# 14sbms_sch.net
KiCad netlist of a schematic drawn in EAGLE
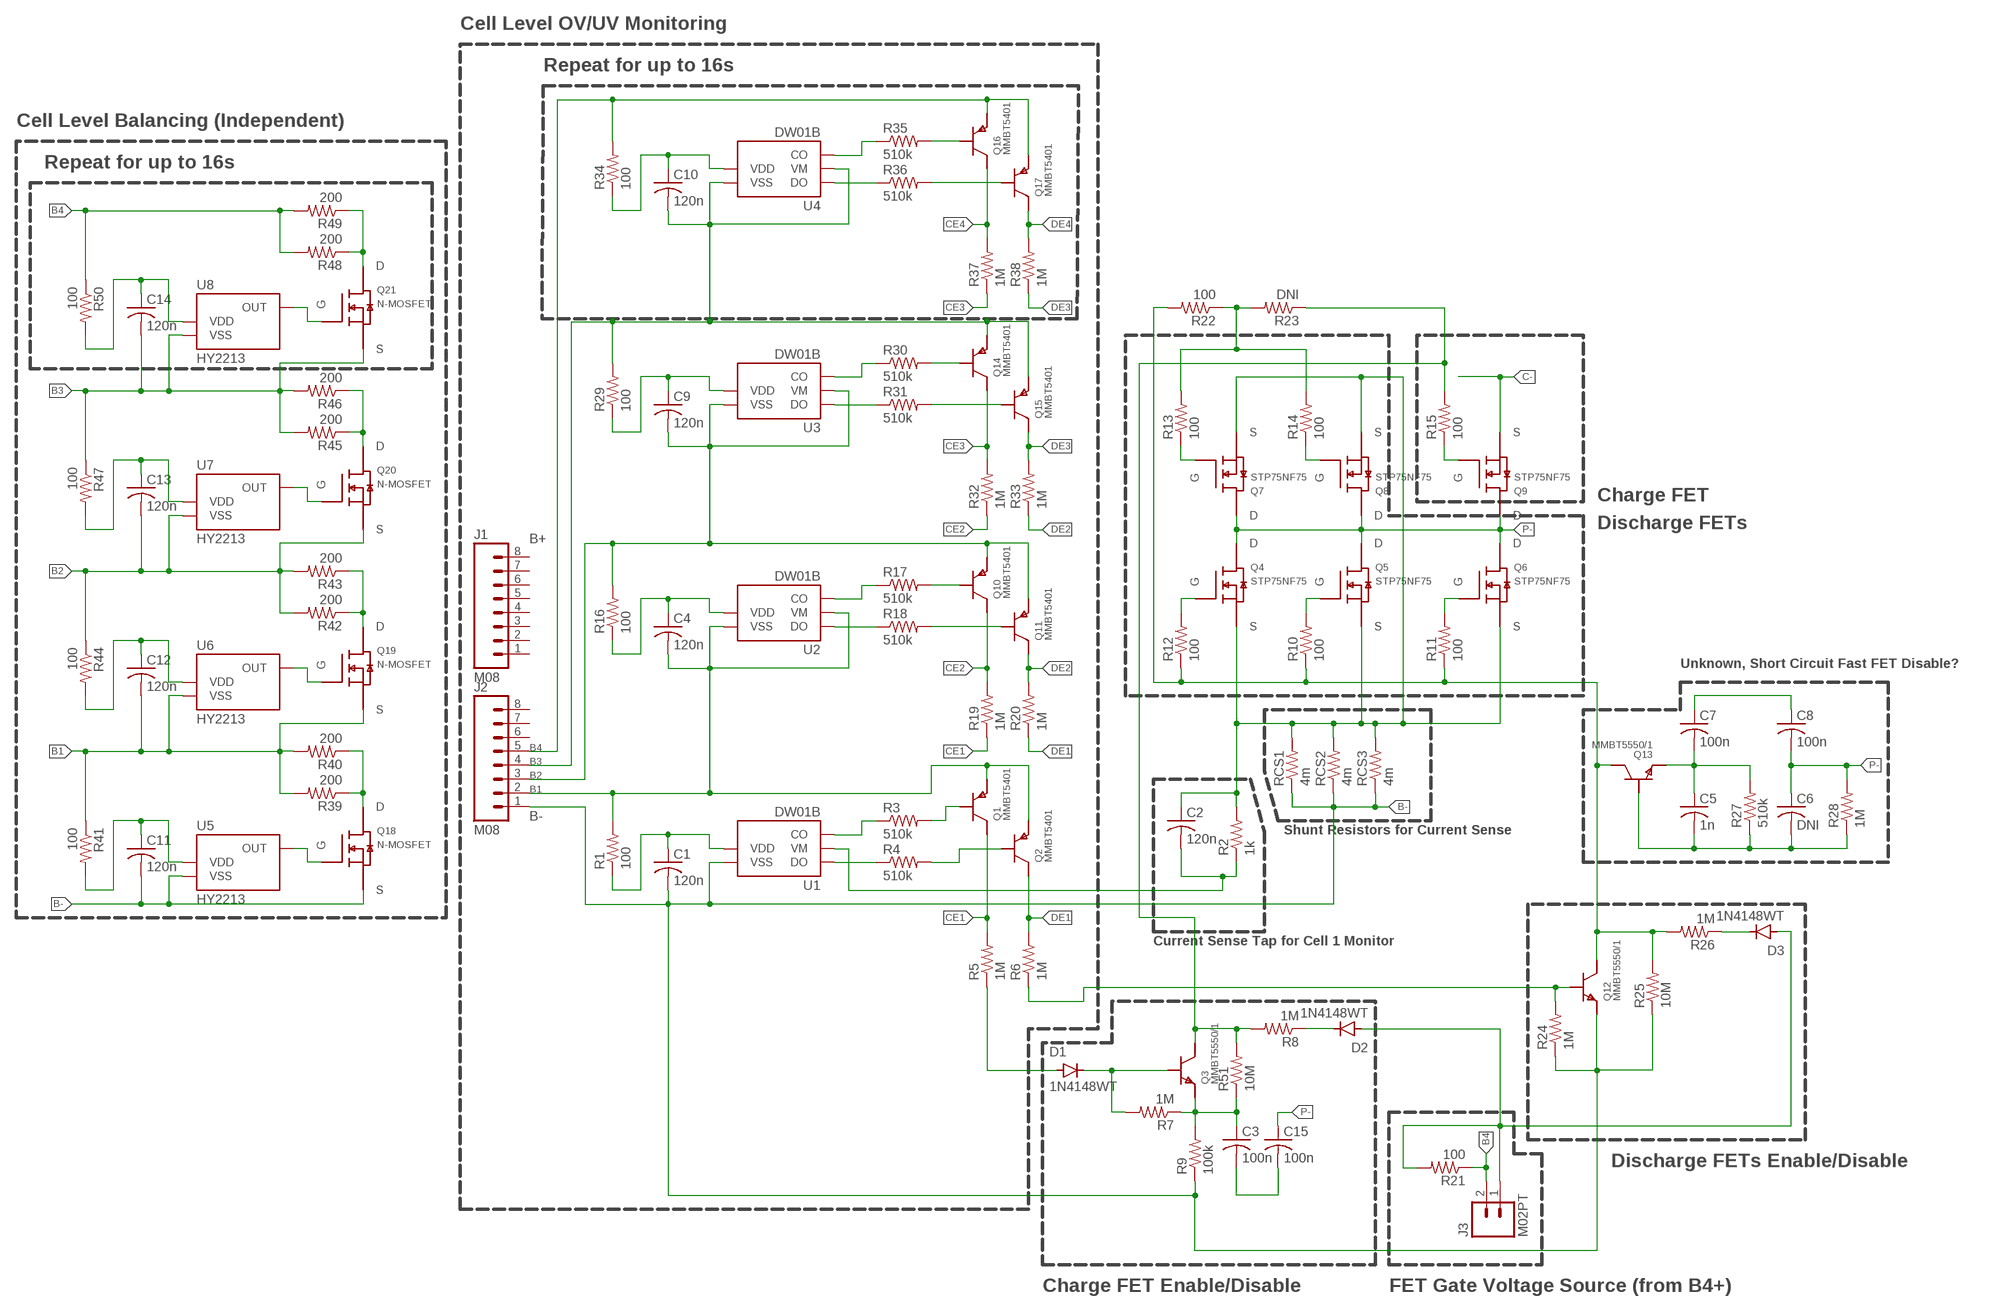
[diagram p0: schematic, sheet 1]

(export (version "E")
  (design (tool "Eeschema 10.0.6"))
  (components
    (comp (ref "C1")
      (value "120n")
      (footprint "eagle-import:C0603")
      (libsource (lib "eagle-import") (part "C-USC0603"))
    )
    (comp (ref "C2")
      (value "120n")
      (footprint "eagle-import:C0603")
      (libsource (lib "eagle-import") (part "C-USC0603"))
    )
    (comp (ref "C3")
      (value "100n")
      (footprint "eagle-import:C0603")
      (libsource (lib "eagle-import") (part "C-USC0603"))
    )
    (comp (ref "C4")
      (value "120n")
      (footprint "eagle-import:C0603")
      (libsource (lib "eagle-import") (part "C-USC0603"))
    )
    (comp (ref "C5")
      (value "1n")
      (footprint "eagle-import:C0603")
      (libsource (lib "eagle-import") (part "C-USC0603"))
    )
    (comp (ref "C6")
      (value "DNI")
      (footprint "eagle-import:C0603")
      (libsource (lib "eagle-import") (part "C-USC0603"))
    )
    (comp (ref "C7")
      (value "100n")
      (footprint "eagle-import:C0805")
      (libsource (lib "eagle-import") (part "C-USC0805"))
    )
    (comp (ref "C8")
      (value "100n")
      (footprint "eagle-import:C0805")
      (libsource (lib "eagle-import") (part "C-USC0805"))
    )
    (comp (ref "C9")
      (value "120n")
      (footprint "eagle-import:C0603")
      (libsource (lib "eagle-import") (part "C-USC0603"))
    )
    (comp (ref "C10")
      (value "120n")
      (footprint "eagle-import:C0603")
      (libsource (lib "eagle-import") (part "C-USC0603"))
    )
    (comp (ref "C11")
      (value "120n")
      (footprint "eagle-import:C0603")
      (libsource (lib "eagle-import") (part "C-USC0603"))
    )
    (comp (ref "C12")
      (value "120n")
      (footprint "eagle-import:C0603")
      (libsource (lib "eagle-import") (part "C-USC0603"))
    )
    (comp (ref "C13")
      (value "120n")
      (footprint "eagle-import:C0603")
      (libsource (lib "eagle-import") (part "C-USC0603"))
    )
    (comp (ref "C14")
      (value "120n")
      (footprint "eagle-import:C0603")
      (libsource (lib "eagle-import") (part "C-USC0603"))
    )
    (comp (ref "C15")
      (value "100n")
      (footprint "eagle-import:C0603")
      (libsource (lib "eagle-import") (part "C-USC0603"))
    )
    (comp (ref "D1")
      (value "1N4148WT")
      (footprint "eagle-import:SOD523")
      (libsource (lib "eagle-import") (part "1N4148WT"))
    )
    (comp (ref "D2")
      (value "1N4148WT")
      (footprint "eagle-import:SOD523")
      (libsource (lib "eagle-import") (part "1N4148WT"))
    )
    (comp (ref "D3")
      (value "1N4148WT")
      (footprint "eagle-import:SOD523")
      (libsource (lib "eagle-import") (part "1N4148WT"))
    )
    (comp (ref "J1")
      (value "M08")
      (footprint "eagle-import:S8B-XH-A")
      (libsource (lib "eagle-import") (part "M08"))
    )
    (comp (ref "J2")
      (value "M08")
      (footprint "eagle-import:S8B-XH-A")
      (libsource (lib "eagle-import") (part "M08"))
    )
    (comp (ref "J3")
      (value "M02PT")
      (footprint "eagle-import:PHOENIXCONTACT1935161")
      (libsource (lib "eagle-import") (part "M02PT"))
    )
    (comp (ref "Q1")
      (value "MMBT5401")
      (footprint "eagle-import:SOT23")
      (libsource (lib "eagle-import") (part "MMBT5401"))
    )
    (comp (ref "Q2")
      (value "MMBT5401")
      (footprint "eagle-import:SOT23")
      (libsource (lib "eagle-import") (part "MMBT5401"))
    )
    (comp (ref "Q3")
      (value "MMBT5550/1")
      (footprint "eagle-import:SOT23")
      (libsource (lib "eagle-import") (part "MMBT5550/1"))
    )
    (comp (ref "Q4")
      (value "STP75NF75")
      (footprint "eagle-import:D2PAK-ST")
      (libsource (lib "eagle-import") (part "STP75NF75"))
    )
    (comp (ref "Q5")
      (value "STP75NF75")
      (footprint "eagle-import:D2PAK-ST")
      (libsource (lib "eagle-import") (part "STP75NF75"))
    )
    (comp (ref "Q6")
      (value "STP75NF75")
      (footprint "eagle-import:D2PAK-ST")
      (libsource (lib "eagle-import") (part "STP75NF75"))
    )
    (comp (ref "Q7")
      (value "STP75NF75")
      (footprint "eagle-import:D2PAK-ST")
      (libsource (lib "eagle-import") (part "STP75NF75"))
    )
    (comp (ref "Q8")
      (value "STP75NF75")
      (footprint "eagle-import:D2PAK-ST")
      (libsource (lib "eagle-import") (part "STP75NF75"))
    )
    (comp (ref "Q9")
      (value "STP75NF75")
      (footprint "eagle-import:D2PAK-ST")
      (libsource (lib "eagle-import") (part "STP75NF75"))
    )
    (comp (ref "Q10")
      (value "MMBT5401")
      (footprint "eagle-import:SOT23")
      (libsource (lib "eagle-import") (part "MMBT5401"))
    )
    (comp (ref "Q11")
      (value "MMBT5401")
      (footprint "eagle-import:SOT23")
      (libsource (lib "eagle-import") (part "MMBT5401"))
    )
    (comp (ref "Q12")
      (value "MMBT5550/1")
      (footprint "eagle-import:SOT23")
      (libsource (lib "eagle-import") (part "MMBT5550/1"))
    )
    (comp (ref "Q13")
      (value "MMBT5550/1")
      (footprint "eagle-import:SOT23")
      (libsource (lib "eagle-import") (part "MMBT5550/1"))
    )
    (comp (ref "Q14")
      (value "MMBT5401")
      (footprint "eagle-import:SOT23")
      (libsource (lib "eagle-import") (part "MMBT5401"))
    )
    (comp (ref "Q15")
      (value "MMBT5401")
      (footprint "eagle-import:SOT23")
      (libsource (lib "eagle-import") (part "MMBT5401"))
    )
    (comp (ref "Q16")
      (value "MMBT5401")
      (footprint "eagle-import:SOT23")
      (libsource (lib "eagle-import") (part "MMBT5401"))
    )
    (comp (ref "Q17")
      (value "MMBT5401")
      (footprint "eagle-import:SOT23")
      (libsource (lib "eagle-import") (part "MMBT5401"))
    )
    (comp (ref "Q18")
      (value "N-MOSFET")
      (footprint "eagle-import:SOT23")
      (libsource (lib "eagle-import") (part "N-MOSFET"))
    )
    (comp (ref "Q19")
      (value "N-MOSFET")
      (footprint "eagle-import:SOT23")
      (libsource (lib "eagle-import") (part "N-MOSFET"))
    )
    (comp (ref "Q20")
      (value "N-MOSFET")
      (footprint "eagle-import:SOT23")
      (libsource (lib "eagle-import") (part "N-MOSFET"))
    )
    (comp (ref "Q21")
      (value "N-MOSFET")
      (footprint "eagle-import:SOT23")
      (libsource (lib "eagle-import") (part "N-MOSFET"))
    )
    (comp (ref "R1")
      (value "100")
      (footprint "eagle-import:R0603")
      (libsource (lib "eagle-import") (part "R-US_R0603"))
    )
    (comp (ref "R2")
      (value "1k")
      (footprint "eagle-import:R0603")
      (libsource (lib "eagle-import") (part "R-US_R0603"))
    )
    (comp (ref "R3")
      (value "510k")
      (footprint "eagle-import:R0603")
      (libsource (lib "eagle-import") (part "R-US_R0603"))
    )
    (comp (ref "R4")
      (value "510k")
      (footprint "eagle-import:R0603")
      (libsource (lib "eagle-import") (part "R-US_R0603"))
    )
    (comp (ref "R5")
      (value "1M")
      (footprint "eagle-import:R0603")
      (libsource (lib "eagle-import") (part "R-US_R0603"))
    )
    (comp (ref "R6")
      (value "1M")
      (footprint "eagle-import:R0603")
      (libsource (lib "eagle-import") (part "R-US_R0603"))
    )
    (comp (ref "R7")
      (value "1M")
      (footprint "eagle-import:R0603")
      (libsource (lib "eagle-import") (part "R-US_R0603"))
    )
    (comp (ref "R8")
      (value "1M")
      (footprint "eagle-import:R0603")
      (libsource (lib "eagle-import") (part "R-US_R0603"))
    )
    (comp (ref "R9")
      (value "100k")
      (footprint "eagle-import:R0603")
      (libsource (lib "eagle-import") (part "R-US_R0603"))
    )
    (comp (ref "R10")
      (value "100")
      (footprint "eagle-import:R0603")
      (libsource (lib "eagle-import") (part "R-US_R0603"))
    )
    (comp (ref "R11")
      (value "100")
      (footprint "eagle-import:R0603")
      (libsource (lib "eagle-import") (part "R-US_R0603"))
    )
    (comp (ref "R12")
      (value "100")
      (footprint "eagle-import:R0603")
      (libsource (lib "eagle-import") (part "R-US_R0603"))
    )
    (comp (ref "R13")
      (value "100")
      (footprint "eagle-import:R0603")
      (libsource (lib "eagle-import") (part "R-US_R0603"))
    )
    (comp (ref "R14")
      (value "100")
      (footprint "eagle-import:R0603")
      (libsource (lib "eagle-import") (part "R-US_R0603"))
    )
    (comp (ref "R15")
      (value "100")
      (footprint "eagle-import:R0603")
      (libsource (lib "eagle-import") (part "R-US_R0603"))
    )
    (comp (ref "R16")
      (value "100")
      (footprint "eagle-import:R0603")
      (libsource (lib "eagle-import") (part "R-US_R0603"))
    )
    (comp (ref "R17")
      (value "510k")
      (footprint "eagle-import:R0603")
      (libsource (lib "eagle-import") (part "R-US_R0603"))
    )
    (comp (ref "R18")
      (value "510k")
      (footprint "eagle-import:R0603")
      (libsource (lib "eagle-import") (part "R-US_R0603"))
    )
    (comp (ref "R19")
      (value "1M")
      (footprint "eagle-import:R0603")
      (libsource (lib "eagle-import") (part "R-US_R0603"))
    )
    (comp (ref "R20")
      (value "1M")
      (footprint "eagle-import:R0603")
      (libsource (lib "eagle-import") (part "R-US_R0603"))
    )
    (comp (ref "R21")
      (value "100")
      (footprint "eagle-import:R0603")
      (libsource (lib "eagle-import") (part "R-US_R0603"))
    )
    (comp (ref "R22")
      (value "100")
      (footprint "eagle-import:R0603")
      (libsource (lib "eagle-import") (part "R-US_R0603"))
    )
    (comp (ref "R23")
      (value "DNI")
      (footprint "eagle-import:R0603")
      (libsource (lib "eagle-import") (part "R-US_R0603"))
    )
    (comp (ref "R24")
      (value "1M")
      (footprint "eagle-import:R0603")
      (libsource (lib "eagle-import") (part "R-US_R0603"))
    )
    (comp (ref "R25")
      (value "10M")
      (footprint "eagle-import:R0603")
      (libsource (lib "eagle-import") (part "R-US_R0603"))
    )
    (comp (ref "R26")
      (value "1M")
      (footprint "eagle-import:R0603")
      (libsource (lib "eagle-import") (part "R-US_R0603"))
    )
    (comp (ref "R27")
      (value "510k")
      (footprint "eagle-import:R0603")
      (libsource (lib "eagle-import") (part "R-US_R0603"))
    )
    (comp (ref "R28")
      (value "1M")
      (footprint "eagle-import:R0603")
      (libsource (lib "eagle-import") (part "R-US_R0603"))
    )
    (comp (ref "R29")
      (value "100")
      (footprint "eagle-import:R0603")
      (libsource (lib "eagle-import") (part "R-US_R0603"))
    )
    (comp (ref "R30")
      (value "510k")
      (footprint "eagle-import:R0603")
      (libsource (lib "eagle-import") (part "R-US_R0603"))
    )
    (comp (ref "R31")
      (value "510k")
      (footprint "eagle-import:R0603")
      (libsource (lib "eagle-import") (part "R-US_R0603"))
    )
    (comp (ref "R32")
      (value "1M")
      (footprint "eagle-import:R0603")
      (libsource (lib "eagle-import") (part "R-US_R0603"))
    )
    (comp (ref "R33")
      (value "1M")
      (footprint "eagle-import:R0603")
      (libsource (lib "eagle-import") (part "R-US_R0603"))
    )
    (comp (ref "R34")
      (value "100")
      (footprint "eagle-import:R0603")
      (libsource (lib "eagle-import") (part "R-US_R0603"))
    )
    (comp (ref "R35")
      (value "510k")
      (footprint "eagle-import:R0603")
      (libsource (lib "eagle-import") (part "R-US_R0603"))
    )
    (comp (ref "R36")
      (value "510k")
      (footprint "eagle-import:R0603")
      (libsource (lib "eagle-import") (part "R-US_R0603"))
    )
    (comp (ref "R37")
      (value "1M")
      (footprint "eagle-import:R0603")
      (libsource (lib "eagle-import") (part "R-US_R0603"))
    )
    (comp (ref "R38")
      (value "1M")
      (footprint "eagle-import:R0603")
      (libsource (lib "eagle-import") (part "R-US_R0603"))
    )
    (comp (ref "R39")
      (value "200")
      (footprint "eagle-import:R1206")
      (libsource (lib "eagle-import") (part "R-US_R1206"))
    )
    (comp (ref "R40")
      (value "200")
      (footprint "eagle-import:R1206")
      (libsource (lib "eagle-import") (part "R-US_R1206"))
    )
    (comp (ref "R41")
      (value "100")
      (footprint "eagle-import:R0603")
      (libsource (lib "eagle-import") (part "R-US_R0603"))
    )
    (comp (ref "R42")
      (value "200")
      (footprint "eagle-import:R1206")
      (libsource (lib "eagle-import") (part "R-US_R1206"))
    )
    (comp (ref "R43")
      (value "200")
      (footprint "eagle-import:R1206")
      (libsource (lib "eagle-import") (part "R-US_R1206"))
    )
    (comp (ref "R44")
      (value "100")
      (footprint "eagle-import:R0603")
      (libsource (lib "eagle-import") (part "R-US_R0603"))
    )
    (comp (ref "R45")
      (value "200")
      (footprint "eagle-import:R1206")
      (libsource (lib "eagle-import") (part "R-US_R1206"))
    )
    (comp (ref "R46")
      (value "200")
      (footprint "eagle-import:R1206")
      (libsource (lib "eagle-import") (part "R-US_R1206"))
    )
    (comp (ref "R47")
      (value "100")
      (footprint "eagle-import:R0603")
      (libsource (lib "eagle-import") (part "R-US_R0603"))
    )
    (comp (ref "R48")
      (value "200")
      (footprint "eagle-import:R1206")
      (libsource (lib "eagle-import") (part "R-US_R1206"))
    )
    (comp (ref "R49")
      (value "200")
      (footprint "eagle-import:R1206")
      (libsource (lib "eagle-import") (part "R-US_R1206"))
    )
    (comp (ref "R50")
      (value "100")
      (footprint "eagle-import:R0603")
      (libsource (lib "eagle-import") (part "R-US_R0603"))
    )
    (comp (ref "R51")
      (value "10M")
      (footprint "eagle-import:R0603")
      (libsource (lib "eagle-import") (part "R-US_R0603"))
    )
    (comp (ref "RCS1")
      (value "4m")
      (footprint "eagle-import:R2512")
      (libsource (lib "eagle-import") (part "R-US_R2512"))
    )
    (comp (ref "RCS2")
      (value "4m")
      (footprint "eagle-import:R2512")
      (libsource (lib "eagle-import") (part "R-US_R2512"))
    )
    (comp (ref "RCS3")
      (value "4m")
      (footprint "eagle-import:R2512")
      (libsource (lib "eagle-import") (part "R-US_R2512"))
    )
    (comp (ref "U1")
      (value "DW01B")
      (footprint "eagle-import:SOT23-6")
      (libsource (lib "eagle-import") (part "DW01B"))
    )
    (comp (ref "U2")
      (value "DW01B")
      (footprint "eagle-import:SOT23-6")
      (libsource (lib "eagle-import") (part "DW01B"))
    )
    (comp (ref "U3")
      (value "DW01B")
      (footprint "eagle-import:SOT23-6")
      (libsource (lib "eagle-import") (part "DW01B"))
    )
    (comp (ref "U4")
      (value "DW01B")
      (footprint "eagle-import:SOT23-6")
      (libsource (lib "eagle-import") (part "DW01B"))
    )
    (comp (ref "U5")
      (value "HY2213")
      (footprint "eagle-import:SOT23-6")
      (libsource (lib "eagle-import") (part "HY2213"))
    )
    (comp (ref "U6")
      (value "HY2213")
      (footprint "eagle-import:SOT23-6")
      (libsource (lib "eagle-import") (part "HY2213"))
    )
    (comp (ref "U7")
      (value "HY2213")
      (footprint "eagle-import:SOT23-6")
      (libsource (lib "eagle-import") (part "HY2213"))
    )
    (comp (ref "U8")
      (value "HY2213")
      (footprint "eagle-import:SOT23-6")
      (libsource (lib "eagle-import") (part "HY2213"))
    )
  )
  (nets
    (net (code "1") (name "B-") (class "Default")
      (node (ref "C1") (pin "2") (pinfunction "2_2") (pintype "passive"))
      (node (ref "C11") (pin "2") (pinfunction "2_2") (pintype "passive"))
      (node (ref "J2") (pin "1") (pinfunction "1_1") (pintype "passive"))
      (node (ref "Q12") (pin "2") (pinfunction "E_2") (pintype "bidirectional"))
      (node (ref "Q18") (pin "2") (pinfunction "S_2") (pintype "bidirectional"))
      (node (ref "R24") (pin "1") (pinfunction "1_1") (pintype "passive"))
      (node (ref "R25") (pin "1") (pinfunction "1_1") (pintype "passive"))
      (node (ref "R9") (pin "1") (pinfunction "1_1") (pintype "passive"))
      (node (ref "RCS1") (pin "1") (pinfunction "1_1") (pintype "passive"))
      (node (ref "RCS2") (pin "1") (pinfunction "1_1") (pintype "passive"))
      (node (ref "RCS3") (pin "1") (pinfunction "1_1") (pintype "passive"))
      (node (ref "U1") (pin "6") (pinfunction "VSS_6") (pintype "bidirectional"))
      (node (ref "U5") (pin "3") (pinfunction "VSS_3") (pintype "bidirectional"))
    )
    (net (code "2") (name "B1") (class "Default")
      (node (ref "C12") (pin "2") (pinfunction "2_2") (pintype "passive"))
      (node (ref "C4") (pin "2") (pinfunction "2_2") (pintype "passive"))
      (node (ref "J2") (pin "2") (pinfunction "2_2") (pintype "passive"))
      (node (ref "Q1") (pin "2") (pinfunction "E_2") (pintype "bidirectional"))
      (node (ref "Q19") (pin "2") (pinfunction "S_2") (pintype "bidirectional"))
      (node (ref "Q2") (pin "2") (pinfunction "E_2") (pintype "bidirectional"))
      (node (ref "R1") (pin "2") (pinfunction "2_2") (pintype "passive"))
      (node (ref "R39") (pin "2") (pinfunction "2_2") (pintype "passive"))
      (node (ref "R40") (pin "2") (pinfunction "2_2") (pintype "passive"))
      (node (ref "R41") (pin "1") (pinfunction "1_1") (pintype "passive"))
      (node (ref "U2") (pin "2") (pinfunction "VM_2") (pintype "bidirectional"))
      (node (ref "U2") (pin "6") (pinfunction "VSS_6") (pintype "bidirectional"))
      (node (ref "U6") (pin "3") (pinfunction "VSS_3") (pintype "bidirectional"))
    )
    (net (code "3") (name "B2") (class "Default")
      (node (ref "C13") (pin "2") (pinfunction "2_2") (pintype "passive"))
      (node (ref "C9") (pin "2") (pinfunction "2_2") (pintype "passive"))
      (node (ref "J2") (pin "3") (pinfunction "3_3") (pintype "passive"))
      (node (ref "Q10") (pin "2") (pinfunction "E_2") (pintype "bidirectional"))
      (node (ref "Q11") (pin "2") (pinfunction "E_2") (pintype "bidirectional"))
      (node (ref "Q20") (pin "2") (pinfunction "S_2") (pintype "bidirectional"))
      (node (ref "R16") (pin "2") (pinfunction "2_2") (pintype "passive"))
      (node (ref "R42") (pin "2") (pinfunction "2_2") (pintype "passive"))
      (node (ref "R43") (pin "2") (pinfunction "2_2") (pintype "passive"))
      (node (ref "R44") (pin "1") (pinfunction "1_1") (pintype "passive"))
      (node (ref "U3") (pin "2") (pinfunction "VM_2") (pintype "bidirectional"))
      (node (ref "U3") (pin "6") (pinfunction "VSS_6") (pintype "bidirectional"))
      (node (ref "U7") (pin "3") (pinfunction "VSS_3") (pintype "bidirectional"))
    )
    (net (code "4") (name "B3") (class "Default")
      (node (ref "C10") (pin "2") (pinfunction "2_2") (pintype "passive"))
      (node (ref "C14") (pin "2") (pinfunction "2_2") (pintype "passive"))
      (node (ref "J2") (pin "4") (pinfunction "4_4") (pintype "passive"))
      (node (ref "Q14") (pin "2") (pinfunction "E_2") (pintype "bidirectional"))
      (node (ref "Q15") (pin "2") (pinfunction "E_2") (pintype "bidirectional"))
      (node (ref "Q21") (pin "2") (pinfunction "S_2") (pintype "bidirectional"))
      (node (ref "R29") (pin "2") (pinfunction "2_2") (pintype "passive"))
      (node (ref "R45") (pin "2") (pinfunction "2_2") (pintype "passive"))
      (node (ref "R46") (pin "2") (pinfunction "2_2") (pintype "passive"))
      (node (ref "R47") (pin "1") (pinfunction "1_1") (pintype "passive"))
      (node (ref "U4") (pin "2") (pinfunction "VM_2") (pintype "bidirectional"))
      (node (ref "U4") (pin "6") (pinfunction "VSS_6") (pintype "bidirectional"))
      (node (ref "U8") (pin "3") (pinfunction "VSS_3") (pintype "bidirectional"))
    )
    (net (code "5") (name "B4") (class "Default")
      (node (ref "J2") (pin "5") (pinfunction "5_5") (pintype "passive"))
      (node (ref "J3") (pin "2") (pinfunction "2_2") (pintype "passive"))
      (node (ref "Q16") (pin "2") (pinfunction "E_2") (pintype "bidirectional"))
      (node (ref "Q17") (pin "2") (pinfunction "E_2") (pintype "bidirectional"))
      (node (ref "R21") (pin "1") (pinfunction "1_1") (pintype "passive"))
      (node (ref "R34") (pin "2") (pinfunction "2_2") (pintype "passive"))
      (node (ref "R48") (pin "2") (pinfunction "2_2") (pintype "passive"))
      (node (ref "R49") (pin "2") (pinfunction "2_2") (pintype "passive"))
      (node (ref "R50") (pin "1") (pinfunction "1_1") (pintype "passive"))
    )
    (net (code "6") (name "C-") (class "Default")
      (node (ref "Q9") (pin "3-S") (pinfunction "S_3-S") (pintype "bidirectional"))
    )
    (net (code "7") (name "CE1") (class "Default")
      (node (ref "Q1") (pin "3") (pinfunction "C_3") (pintype "bidirectional"))
      (node (ref "R19") (pin "1") (pinfunction "1_1") (pintype "passive"))
      (node (ref "R5") (pin "2") (pinfunction "2_2") (pintype "passive"))
    )
    (net (code "8") (name "CE2") (class "Default")
      (node (ref "Q10") (pin "3") (pinfunction "C_3") (pintype "bidirectional"))
      (node (ref "R19") (pin "2") (pinfunction "2_2") (pintype "passive"))
      (node (ref "R32") (pin "1") (pinfunction "1_1") (pintype "passive"))
    )
    (net (code "9") (name "CE3") (class "Default")
      (node (ref "Q14") (pin "3") (pinfunction "C_3") (pintype "bidirectional"))
      (node (ref "R32") (pin "2") (pinfunction "2_2") (pintype "passive"))
      (node (ref "R37") (pin "1") (pinfunction "1_1") (pintype "passive"))
    )
    (net (code "10") (name "CE4") (class "Default")
      (node (ref "Q16") (pin "3") (pinfunction "C_3") (pintype "bidirectional"))
      (node (ref "R37") (pin "2") (pinfunction "2_2") (pintype "passive"))
    )
    (net (code "11") (name "DE1") (class "Default")
      (node (ref "Q2") (pin "3") (pinfunction "C_3") (pintype "bidirectional"))
      (node (ref "R20") (pin "1") (pinfunction "1_1") (pintype "passive"))
      (node (ref "R6") (pin "2") (pinfunction "2_2") (pintype "passive"))
    )
    (net (code "12") (name "DE2") (class "Default")
      (node (ref "Q11") (pin "3") (pinfunction "C_3") (pintype "bidirectional"))
      (node (ref "R20") (pin "2") (pinfunction "2_2") (pintype "passive"))
      (node (ref "R33") (pin "1") (pinfunction "1_1") (pintype "passive"))
    )
    (net (code "13") (name "DE3") (class "Default")
      (node (ref "Q15") (pin "3") (pinfunction "C_3") (pintype "bidirectional"))
      (node (ref "R33") (pin "2") (pinfunction "2_2") (pintype "passive"))
      (node (ref "R38") (pin "1") (pinfunction "1_1") (pintype "passive"))
    )
    (net (code "14") (name "DE4") (class "Default")
      (node (ref "Q17") (pin "3") (pinfunction "C_3") (pintype "bidirectional"))
      (node (ref "R38") (pin "2") (pinfunction "2_2") (pintype "passive"))
    )
    (net (code "15") (name "Net-(C7-Pad1)") (class "Default")
      (node (ref "C7") (pin "1") (pinfunction "1_1") (pintype "passive"))
      (node (ref "C8") (pin "1") (pinfunction "1_1") (pintype "passive"))
    )
    (net (code "16") (name "Net-(C15-Pad2)") (class "Default")
      (node (ref "C15") (pin "2") (pinfunction "2_2") (pintype "passive"))
      (node (ref "C3") (pin "2") (pinfunction "2_2") (pintype "passive"))
    )
    (net (code "17") (name "Net-(D1-ANODE)") (class "Default")
      (node (ref "D1") (pin "A") (pinfunction "ANODE_A") (pintype "passive"))
      (node (ref "R5") (pin "1") (pinfunction "1_1") (pintype "passive"))
    )
    (net (code "18") (name "Net-(D1-CATHODE)") (class "Default")
      (node (ref "D1") (pin "K") (pinfunction "CATHODE_K") (pintype "passive"))
      (node (ref "Q3") (pin "1") (pinfunction "B_1") (pintype "bidirectional"))
      (node (ref "R7") (pin "2") (pinfunction "2_2") (pintype "passive"))
    )
    (net (code "19") (name "Net-(D2-ANODE)") (class "Default")
      (node (ref "D2") (pin "A") (pinfunction "ANODE_A") (pintype "passive"))
      (node (ref "D3") (pin "A") (pinfunction "ANODE_A") (pintype "passive"))
      (node (ref "J3") (pin "1") (pinfunction "1_1") (pintype "passive"))
      (node (ref "R21") (pin "2") (pinfunction "2_2") (pintype "passive"))
    )
    (net (code "20") (name "Net-(D2-CATHODE)") (class "Default")
      (node (ref "D2") (pin "K") (pinfunction "CATHODE_K") (pintype "passive"))
      (node (ref "R8") (pin "1") (pinfunction "1_1") (pintype "passive"))
    )
    (net (code "21") (name "Net-(D3-CATHODE)") (class "Default")
      (node (ref "D3") (pin "K") (pinfunction "CATHODE_K") (pintype "passive"))
      (node (ref "R26") (pin "1") (pinfunction "1_1") (pintype "passive"))
    )
    (net (code "22") (name "Net-(Q1-B)") (class "Default")
      (node (ref "Q1") (pin "1") (pinfunction "B_1") (pintype "bidirectional"))
      (node (ref "R3") (pin "2") (pinfunction "2_2") (pintype "passive"))
    )
    (net (code "23") (name "Net-(Q2-B)") (class "Default")
      (node (ref "Q2") (pin "1") (pinfunction "B_1") (pintype "bidirectional"))
      (node (ref "R4") (pin "2") (pinfunction "2_2") (pintype "passive"))
    )
    (net (code "24") (name "Net-(Q3-C)") (class "Default")
      (node (ref "Q3") (pin "3") (pinfunction "C_3") (pintype "bidirectional"))
      (node (ref "R15") (pin "2") (pinfunction "2_2") (pintype "passive"))
      (node (ref "R23") (pin "1") (pinfunction "1_1") (pintype "passive"))
      (node (ref "R51") (pin "2") (pinfunction "2_2") (pintype "passive"))
      (node (ref "R8") (pin "2") (pinfunction "2_2") (pintype "passive"))
    )
    (net (code "25") (name "Net-(Q3-E)") (class "Default")
      (node (ref "C3") (pin "1") (pinfunction "1_1") (pintype "passive"))
      (node (ref "Q3") (pin "2") (pinfunction "E_2") (pintype "bidirectional"))
      (node (ref "R51") (pin "1") (pinfunction "1_1") (pintype "passive"))
      (node (ref "R7") (pin "1") (pinfunction "1_1") (pintype "passive"))
      (node (ref "R9") (pin "2") (pinfunction "2_2") (pintype "passive"))
    )
    (net (code "26") (name "Net-(Q4-G)") (class "Default")
      (node (ref "Q4") (pin "1-G") (pinfunction "G_1-G") (pintype "bidirectional"))
      (node (ref "R12") (pin "2") (pinfunction "2_2") (pintype "passive"))
    )
    (net (code "27") (name "Net-(Q4-S)") (class "Default")
      (node (ref "C2") (pin "1") (pinfunction "1_1") (pintype "passive"))
      (node (ref "Q4") (pin "3-S") (pinfunction "S_3-S") (pintype "bidirectional"))
      (node (ref "Q5") (pin "3-S") (pinfunction "S_3-S") (pintype "bidirectional"))
      (node (ref "Q6") (pin "3-S") (pinfunction "S_3-S") (pintype "bidirectional"))
      (node (ref "Q7") (pin "3-S") (pinfunction "S_3-S") (pintype "bidirectional"))
      (node (ref "Q8") (pin "3-S") (pinfunction "S_3-S") (pintype "bidirectional"))
      (node (ref "R2") (pin "2") (pinfunction "2_2") (pintype "passive"))
      (node (ref "RCS1") (pin "2") (pinfunction "2_2") (pintype "passive"))
      (node (ref "RCS2") (pin "2") (pinfunction "2_2") (pintype "passive"))
      (node (ref "RCS3") (pin "2") (pinfunction "2_2") (pintype "passive"))
    )
    (net (code "28") (name "Net-(Q5-G)") (class "Default")
      (node (ref "Q5") (pin "1-G") (pinfunction "G_1-G") (pintype "bidirectional"))
      (node (ref "R10") (pin "2") (pinfunction "2_2") (pintype "passive"))
    )
    (net (code "29") (name "Net-(Q6-G)") (class "Default")
      (node (ref "Q6") (pin "1-G") (pinfunction "G_1-G") (pintype "bidirectional"))
      (node (ref "R11") (pin "2") (pinfunction "2_2") (pintype "passive"))
    )
    (net (code "30") (name "Net-(Q7-G)") (class "Default")
      (node (ref "Q7") (pin "1-G") (pinfunction "G_1-G") (pintype "bidirectional"))
      (node (ref "R13") (pin "1") (pinfunction "1_1") (pintype "passive"))
    )
    (net (code "31") (name "Net-(Q8-G)") (class "Default")
      (node (ref "Q8") (pin "1-G") (pinfunction "G_1-G") (pintype "bidirectional"))
      (node (ref "R14") (pin "1") (pinfunction "1_1") (pintype "passive"))
    )
    (net (code "32") (name "Net-(Q9-G)") (class "Default")
      (node (ref "Q9") (pin "1-G") (pinfunction "G_1-G") (pintype "bidirectional"))
      (node (ref "R15") (pin "1") (pinfunction "1_1") (pintype "passive"))
    )
    (net (code "33") (name "Net-(Q10-B)") (class "Default")
      (node (ref "Q10") (pin "1") (pinfunction "B_1") (pintype "bidirectional"))
      (node (ref "R17") (pin "2") (pinfunction "2_2") (pintype "passive"))
    )
    (net (code "34") (name "Net-(Q11-B)") (class "Default")
      (node (ref "Q11") (pin "1") (pinfunction "B_1") (pintype "bidirectional"))
      (node (ref "R18") (pin "2") (pinfunction "2_2") (pintype "passive"))
    )
    (net (code "35") (name "Net-(Q12-B)") (class "Default")
      (node (ref "Q12") (pin "1") (pinfunction "B_1") (pintype "bidirectional"))
      (node (ref "R24") (pin "2") (pinfunction "2_2") (pintype "passive"))
      (node (ref "R6") (pin "1") (pinfunction "1_1") (pintype "passive"))
    )
    (net (code "36") (name "Net-(Q12-C)") (class "Default")
      (node (ref "Q12") (pin "3") (pinfunction "C_3") (pintype "bidirectional"))
      (node (ref "Q13") (pin "3") (pinfunction "C_3") (pintype "bidirectional"))
      (node (ref "R10") (pin "1") (pinfunction "1_1") (pintype "passive"))
      (node (ref "R11") (pin "1") (pinfunction "1_1") (pintype "passive"))
      (node (ref "R12") (pin "1") (pinfunction "1_1") (pintype "passive"))
      (node (ref "R22") (pin "2") (pinfunction "2_2") (pintype "passive"))
      (node (ref "R25") (pin "2") (pinfunction "2_2") (pintype "passive"))
      (node (ref "R26") (pin "2") (pinfunction "2_2") (pintype "passive"))
    )
    (net (code "37") (name "Net-(Q13-B)") (class "Default")
      (node (ref "C5") (pin "2") (pinfunction "2_2") (pintype "passive"))
      (node (ref "C6") (pin "2") (pinfunction "2_2") (pintype "passive"))
      (node (ref "Q13") (pin "1") (pinfunction "B_1") (pintype "bidirectional"))
      (node (ref "R27") (pin "1") (pinfunction "1_1") (pintype "passive"))
      (node (ref "R28") (pin "1") (pinfunction "1_1") (pintype "passive"))
    )
    (net (code "38") (name "Net-(Q13-E)") (class "Default")
      (node (ref "C5") (pin "1") (pinfunction "1_1") (pintype "passive"))
      (node (ref "C7") (pin "2") (pinfunction "2_2") (pintype "passive"))
      (node (ref "Q13") (pin "2") (pinfunction "E_2") (pintype "bidirectional"))
      (node (ref "R27") (pin "2") (pinfunction "2_2") (pintype "passive"))
    )
    (net (code "39") (name "Net-(Q14-B)") (class "Default")
      (node (ref "Q14") (pin "1") (pinfunction "B_1") (pintype "bidirectional"))
      (node (ref "R30") (pin "2") (pinfunction "2_2") (pintype "passive"))
    )
    (net (code "40") (name "Net-(Q15-B)") (class "Default")
      (node (ref "Q15") (pin "1") (pinfunction "B_1") (pintype "bidirectional"))
      (node (ref "R31") (pin "2") (pinfunction "2_2") (pintype "passive"))
    )
    (net (code "41") (name "Net-(Q16-B)") (class "Default")
      (node (ref "Q16") (pin "1") (pinfunction "B_1") (pintype "bidirectional"))
      (node (ref "R35") (pin "2") (pinfunction "2_2") (pintype "passive"))
    )
    (net (code "42") (name "Net-(Q17-B)") (class "Default")
      (node (ref "Q17") (pin "1") (pinfunction "B_1") (pintype "bidirectional"))
      (node (ref "R36") (pin "2") (pinfunction "2_2") (pintype "passive"))
    )
    (net (code "43") (name "Net-(Q18-D)") (class "Default")
      (node (ref "Q18") (pin "3") (pinfunction "D_3") (pintype "bidirectional"))
      (node (ref "R39") (pin "1") (pinfunction "1_1") (pintype "passive"))
      (node (ref "R40") (pin "1") (pinfunction "1_1") (pintype "passive"))
    )
    (net (code "44") (name "Net-(Q18-G)") (class "Default")
      (node (ref "Q18") (pin "1") (pinfunction "G_1") (pintype "bidirectional"))
      (node (ref "U5") (pin "6") (pinfunction "OUT_6") (pintype "bidirectional"))
    )
    (net (code "45") (name "Net-(Q19-D)") (class "Default")
      (node (ref "Q19") (pin "3") (pinfunction "D_3") (pintype "bidirectional"))
      (node (ref "R42") (pin "1") (pinfunction "1_1") (pintype "passive"))
      (node (ref "R43") (pin "1") (pinfunction "1_1") (pintype "passive"))
    )
    (net (code "46") (name "Net-(Q19-G)") (class "Default")
      (node (ref "Q19") (pin "1") (pinfunction "G_1") (pintype "bidirectional"))
      (node (ref "U6") (pin "6") (pinfunction "OUT_6") (pintype "bidirectional"))
    )
    (net (code "47") (name "Net-(Q20-D)") (class "Default")
      (node (ref "Q20") (pin "3") (pinfunction "D_3") (pintype "bidirectional"))
      (node (ref "R45") (pin "1") (pinfunction "1_1") (pintype "passive"))
      (node (ref "R46") (pin "1") (pinfunction "1_1") (pintype "passive"))
    )
    (net (code "48") (name "Net-(Q20-G)") (class "Default")
      (node (ref "Q20") (pin "1") (pinfunction "G_1") (pintype "bidirectional"))
      (node (ref "U7") (pin "6") (pinfunction "OUT_6") (pintype "bidirectional"))
    )
    (net (code "49") (name "Net-(Q21-D)") (class "Default")
      (node (ref "Q21") (pin "3") (pinfunction "D_3") (pintype "bidirectional"))
      (node (ref "R48") (pin "1") (pinfunction "1_1") (pintype "passive"))
      (node (ref "R49") (pin "1") (pinfunction "1_1") (pintype "passive"))
    )
    (net (code "50") (name "Net-(Q21-G)") (class "Default")
      (node (ref "Q21") (pin "1") (pinfunction "G_1") (pintype "bidirectional"))
      (node (ref "U8") (pin "6") (pinfunction "OUT_6") (pintype "bidirectional"))
    )
    (net (code "51") (name "Net-(R13-Pad2)") (class "Default")
      (node (ref "R13") (pin "2") (pinfunction "2_2") (pintype "passive"))
      (node (ref "R14") (pin "2") (pinfunction "2_2") (pintype "passive"))
      (node (ref "R22") (pin "1") (pinfunction "1_1") (pintype "passive"))
      (node (ref "R23") (pin "2") (pinfunction "2_2") (pintype "passive"))
    )
    (net (code "52") (name "Net-(U1-CO)") (class "Default")
      (node (ref "R3") (pin "1") (pinfunction "1_1") (pintype "passive"))
      (node (ref "U1") (pin "3") (pinfunction "CO_3") (pintype "bidirectional"))
    )
    (net (code "53") (name "Net-(U1-DO)") (class "Default")
      (node (ref "R4") (pin "1") (pinfunction "1_1") (pintype "passive"))
      (node (ref "U1") (pin "1") (pinfunction "DO_1") (pintype "bidirectional"))
    )
    (net (code "54") (name "Net-(U1-VDD)") (class "Default")
      (node (ref "C1") (pin "1") (pinfunction "1_1") (pintype "passive"))
      (node (ref "R1") (pin "1") (pinfunction "1_1") (pintype "passive"))
      (node (ref "U1") (pin "5") (pinfunction "VDD_5") (pintype "bidirectional"))
    )
    (net (code "55") (name "Net-(U1-VM)") (class "Default")
      (node (ref "C2") (pin "2") (pinfunction "2_2") (pintype "passive"))
      (node (ref "R2") (pin "1") (pinfunction "1_1") (pintype "passive"))
      (node (ref "U1") (pin "2") (pinfunction "VM_2") (pintype "bidirectional"))
    )
    (net (code "56") (name "Net-(U2-CO)") (class "Default")
      (node (ref "R17") (pin "1") (pinfunction "1_1") (pintype "passive"))
      (node (ref "U2") (pin "3") (pinfunction "CO_3") (pintype "bidirectional"))
    )
    (net (code "57") (name "Net-(U2-DO)") (class "Default")
      (node (ref "R18") (pin "1") (pinfunction "1_1") (pintype "passive"))
      (node (ref "U2") (pin "1") (pinfunction "DO_1") (pintype "bidirectional"))
    )
    (net (code "58") (name "Net-(U2-VDD)") (class "Default")
      (node (ref "C4") (pin "1") (pinfunction "1_1") (pintype "passive"))
      (node (ref "R16") (pin "1") (pinfunction "1_1") (pintype "passive"))
      (node (ref "U2") (pin "5") (pinfunction "VDD_5") (pintype "bidirectional"))
    )
    (net (code "59") (name "Net-(U3-CO)") (class "Default")
      (node (ref "R30") (pin "1") (pinfunction "1_1") (pintype "passive"))
      (node (ref "U3") (pin "3") (pinfunction "CO_3") (pintype "bidirectional"))
    )
    (net (code "60") (name "Net-(U3-DO)") (class "Default")
      (node (ref "R31") (pin "1") (pinfunction "1_1") (pintype "passive"))
      (node (ref "U3") (pin "1") (pinfunction "DO_1") (pintype "bidirectional"))
    )
    (net (code "61") (name "Net-(U3-VDD)") (class "Default")
      (node (ref "C9") (pin "1") (pinfunction "1_1") (pintype "passive"))
      (node (ref "R29") (pin "1") (pinfunction "1_1") (pintype "passive"))
      (node (ref "U3") (pin "5") (pinfunction "VDD_5") (pintype "bidirectional"))
    )
    (net (code "62") (name "Net-(U4-CO)") (class "Default")
      (node (ref "R35") (pin "1") (pinfunction "1_1") (pintype "passive"))
      (node (ref "U4") (pin "3") (pinfunction "CO_3") (pintype "bidirectional"))
    )
    (net (code "63") (name "Net-(U4-DO)") (class "Default")
      (node (ref "R36") (pin "1") (pinfunction "1_1") (pintype "passive"))
      (node (ref "U4") (pin "1") (pinfunction "DO_1") (pintype "bidirectional"))
    )
    (net (code "64") (name "Net-(U4-VDD)") (class "Default")
      (node (ref "C10") (pin "1") (pinfunction "1_1") (pintype "passive"))
      (node (ref "R34") (pin "1") (pinfunction "1_1") (pintype "passive"))
      (node (ref "U4") (pin "5") (pinfunction "VDD_5") (pintype "bidirectional"))
    )
    (net (code "65") (name "Net-(U5-VDD)") (class "Default")
      (node (ref "C11") (pin "1") (pinfunction "1_1") (pintype "passive"))
      (node (ref "R41") (pin "2") (pinfunction "2_2") (pintype "passive"))
      (node (ref "U5") (pin "2") (pinfunction "VDD_2") (pintype "bidirectional"))
    )
    (net (code "66") (name "Net-(U6-VDD)") (class "Default")
      (node (ref "C12") (pin "1") (pinfunction "1_1") (pintype "passive"))
      (node (ref "R44") (pin "2") (pinfunction "2_2") (pintype "passive"))
      (node (ref "U6") (pin "2") (pinfunction "VDD_2") (pintype "bidirectional"))
    )
    (net (code "67") (name "Net-(U7-VDD)") (class "Default")
      (node (ref "C13") (pin "1") (pinfunction "1_1") (pintype "passive"))
      (node (ref "R47") (pin "2") (pinfunction "2_2") (pintype "passive"))
      (node (ref "U7") (pin "2") (pinfunction "VDD_2") (pintype "bidirectional"))
    )
    (net (code "68") (name "Net-(U8-VDD)") (class "Default")
      (node (ref "C14") (pin "1") (pinfunction "1_1") (pintype "passive"))
      (node (ref "R50") (pin "2") (pinfunction "2_2") (pintype "passive"))
      (node (ref "U8") (pin "2") (pinfunction "VDD_2") (pintype "bidirectional"))
    )
    (net (code "69") (name "P-") (class "Default")
      (node (ref "C15") (pin "1") (pinfunction "1_1") (pintype "passive"))
      (node (ref "C6") (pin "1") (pinfunction "1_1") (pintype "passive"))
      (node (ref "C8") (pin "2") (pinfunction "2_2") (pintype "passive"))
      (node (ref "Q4") (pin "2-D") (pinfunction "D_2-D") (pintype "bidirectional"))
      (node (ref "Q5") (pin "2-D") (pinfunction "D_2-D") (pintype "bidirectional"))
      (node (ref "Q6") (pin "2-D") (pinfunction "D_2-D") (pintype "bidirectional"))
      (node (ref "Q7") (pin "2-D") (pinfunction "D_2-D") (pintype "bidirectional"))
      (node (ref "Q8") (pin "2-D") (pinfunction "D_2-D") (pintype "bidirectional"))
      (node (ref "Q9") (pin "2-D") (pinfunction "D_2-D") (pintype "bidirectional"))
      (node (ref "R28") (pin "2") (pinfunction "2_2") (pintype "passive"))
    )
    (net (code "70") (name "unconnected-(J1-Pad1)") (class "Default")
      (node (ref "J1") (pin "1") (pinfunction "1_1") (pintype "passive"))
    )
    (net (code "71") (name "unconnected-(J1-Pad2)") (class "Default")
      (node (ref "J1") (pin "2") (pinfunction "2_2") (pintype "passive"))
    )
    (net (code "72") (name "unconnected-(J1-Pad3)") (class "Default")
      (node (ref "J1") (pin "3") (pinfunction "3_3") (pintype "passive"))
    )
    (net (code "73") (name "unconnected-(J1-Pad4)") (class "Default")
      (node (ref "J1") (pin "4") (pinfunction "4_4") (pintype "passive"))
    )
    (net (code "74") (name "unconnected-(J1-Pad5)") (class "Default")
      (node (ref "J1") (pin "5") (pinfunction "5_5") (pintype "passive"))
    )
    (net (code "75") (name "unconnected-(J1-Pad6)") (class "Default")
      (node (ref "J1") (pin "6") (pinfunction "6_6") (pintype "passive"))
    )
    (net (code "76") (name "unconnected-(J1-Pad7)") (class "Default")
      (node (ref "J1") (pin "7") (pinfunction "7_7") (pintype "passive"))
    )
    (net (code "77") (name "unconnected-(J1-Pad8)") (class "Default")
      (node (ref "J1") (pin "8") (pinfunction "8_8") (pintype "passive"))
    )
    (net (code "78") (name "unconnected-(J2-Pad6)") (class "Default")
      (node (ref "J2") (pin "6") (pinfunction "6_6") (pintype "passive"))
    )
    (net (code "79") (name "unconnected-(J2-Pad7)") (class "Default")
      (node (ref "J2") (pin "7") (pinfunction "7_7") (pintype "passive"))
    )
    (net (code "80") (name "unconnected-(J2-Pad8)") (class "Default")
      (node (ref "J2") (pin "8") (pinfunction "8_8") (pintype "passive"))
    )
  )
)
